# 02.net
KiCad netlist of a schematic drawn in Altium Designer
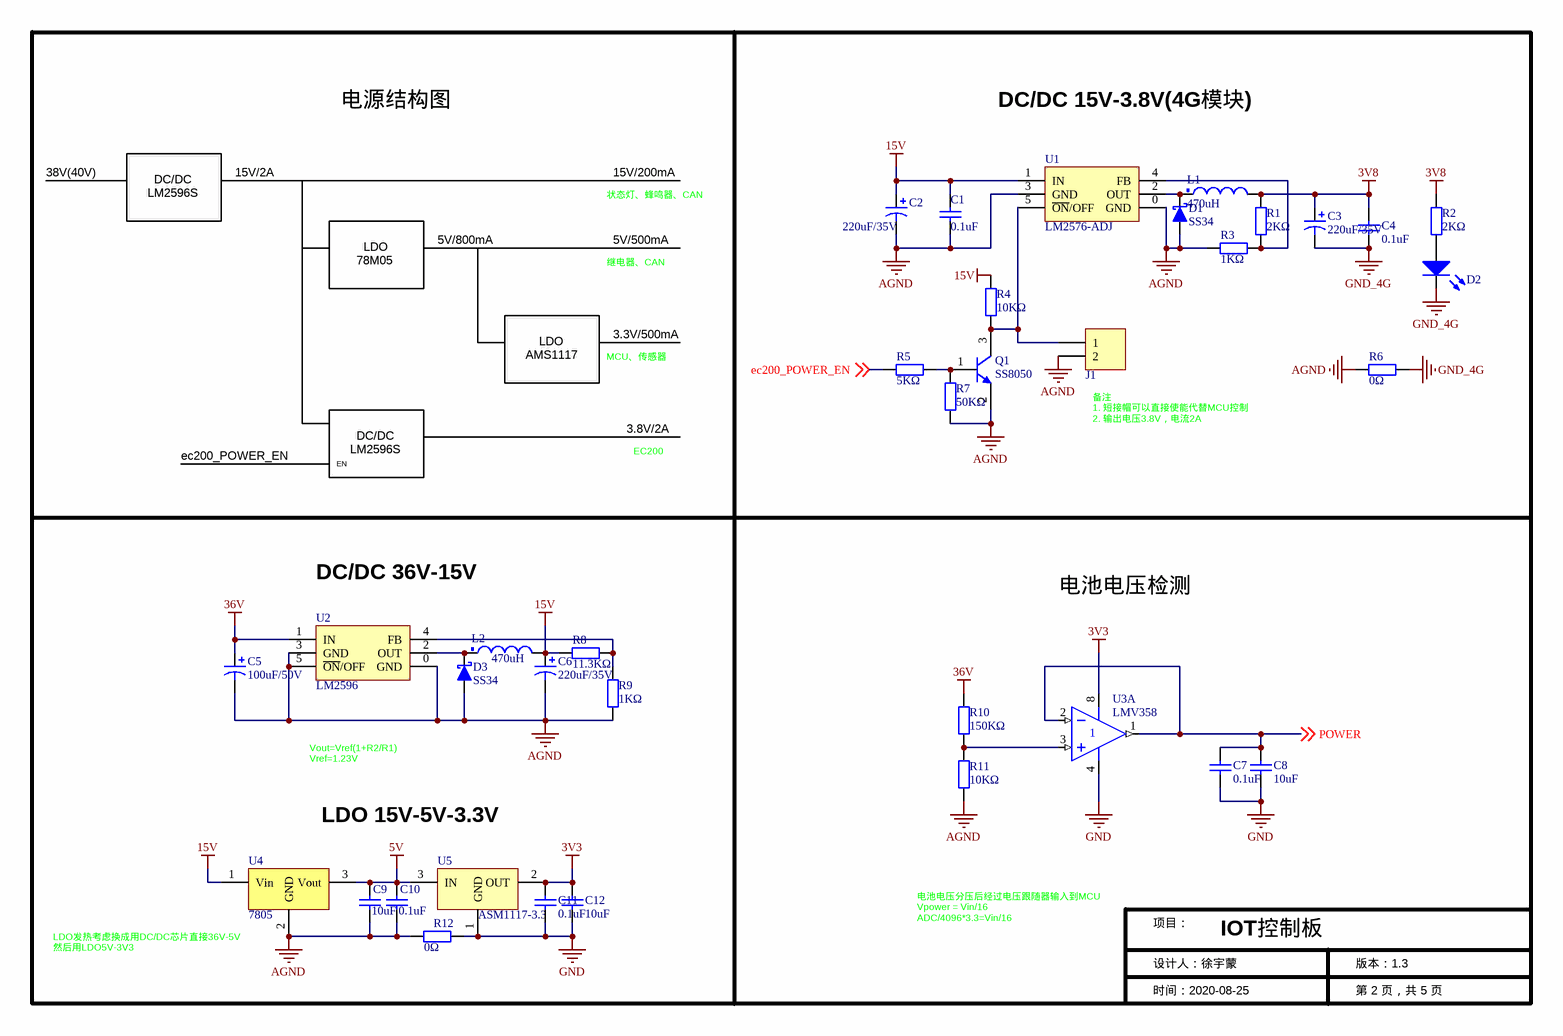
[diagram p0: 02_电源部分.SchDoc]

(export (version "E")
  (design (tool "Eeschema 10.0.6"))
  (components
    (comp (ref "C1")
      (value "0.1uF")
      (footprint "CAP-0603")
      (description "无极性电容")
      (fields (field (name "Comment") "Cap") (field (name "PUBLISHER") "Altium Limited"))
      (libsource (lib "Arrowy_Racing") (part "Cap"))
    )
    (comp (ref "C2")
      (value "220uF/35V")
      (footprint "Cap8x10.5mm")
      (description "贴片电解电容 8*10.5mm")
      (fields (field (name "Comment") "Cap Pol") (field (name "PUBLISHER") "Altium Limited"))
      (libsource (lib "元件库") (part "Cap Pol"))
    )
    (comp (ref "C3")
      (value "220uF/35V")
      (footprint "Cap8x10.5mm")
      (description "贴片电解电容 8*10.5mm")
      (fields (field (name "Comment") "Cap Pol") (field (name "PUBLISHER") "Altium Limited"))
      (libsource (lib "元件库") (part "Cap Pol"))
    )
    (comp (ref "C4")
      (value "0.1uF")
      (footprint "CAP-0603")
      (description "无极性电容")
      (fields (field (name "Comment") "Cap") (field (name "PUBLISHER") "Altium Limited"))
      (libsource (lib "Arrowy_Racing") (part "Cap"))
    )
    (comp (ref "C5")
      (value "100uF/50V")
      (footprint "Cap8x10.5mm")
      (description "贴片电解电容 8*10.5mm")
      (fields (field (name "Comment") "Cap Pol") (field (name "PUBLISHER") "Altium Limited"))
      (libsource (lib "元件库") (part "Cap Pol"))
    )
    (comp (ref "C6")
      (value "220uF/35V")
      (footprint "Cap8x10.5mm")
      (description "贴片电解电容 8*10.5mm")
      (fields (field (name "Comment") "Cap Pol") (field (name "PUBLISHER") "Altium Limited"))
      (libsource (lib "元件库") (part "Cap Pol"))
    )
    (comp (ref "C7")
      (value "0.1uF")
      (footprint "CAP-0603")
      (description "无极性电容")
      (fields (field (name "Comment") "Cap") (field (name "PUBLISHER") "Altium Limited"))
      (libsource (lib "Arrowy_Racing") (part "Cap"))
    )
    (comp (ref "C8")
      (value "10uF")
      (footprint "CAP-0603")
      (description "无极性电容")
      (fields (field (name "Comment") "Cap") (field (name "PUBLISHER") "Altium Limited"))
      (libsource (lib "Arrowy_Racing") (part "Cap"))
    )
    (comp (ref "C9")
      (value "10uF")
      (footprint "CAP-0603")
      (description "无极性电容")
      (fields (field (name "Comment") "Cap") (field (name "PUBLISHER") "Altium Limited"))
      (libsource (lib "Arrowy_Racing") (part "Cap"))
    )
    (comp (ref "C10")
      (value "0.1uF")
      (footprint "CAP-0603")
      (description "无极性电容")
      (fields (field (name "Comment") "Cap") (field (name "PUBLISHER") "Altium Limited"))
      (libsource (lib "Arrowy_Racing") (part "Cap"))
    )
    (comp (ref "C11")
      (value "0.1uF")
      (footprint "CAP-0603")
      (description "无极性电容")
      (fields (field (name "Comment") "Cap") (field (name "PUBLISHER") "Altium Limited"))
      (libsource (lib "Arrowy_Racing") (part "Cap"))
    )
    (comp (ref "C12")
      (value "10uF")
      (footprint "CAP-0603")
      (description "无极性电容")
      (fields (field (name "Comment") "Cap") (field (name "PUBLISHER") "Altium Limited"))
      (libsource (lib "Arrowy_Racing") (part "Cap"))
    )
    (comp (ref "D1")
      (value "SS34")
      (footprint "SMA(DO-214AC)")
      (description "Schottky Diode")
      (fields (field (name "PUBLISHER") "Altium Limited"))
      (libsource (lib "元件库") (part "D Schottky"))
    )
    (comp (ref "D2")
      (value "LED")
      (footprint "LED_0805")
      (description "发光二极管")
      (fields (field (name "PUBLISHER") "Altium Limited"))
      (libsource (lib "Arrowy_Racing") (part "LED"))
    )
    (comp (ref "D3")
      (value "SS34")
      (footprint "SMA(DO-214AC)")
      (description "Schottky Diode")
      (fields (field (name "PUBLISHER") "Altium Limited"))
      (libsource (lib "元件库") (part "D Schottky"))
    )
    (comp (ref "J1")
      (value "Header 2")
      (footprint "Header_2X1_2.54")
      (description "接插件")
      (fields (field (name "PUBLISHER") "Altium Limited"))
      (libsource (lib "Arrowy_Racing") (part "Header 2"))
    )
    (comp (ref "L1")
      (value "470uH")
      (footprint "CD43")
      (description "贴片功率电感")
      (fields (field (name "Comment") "Inductor") (field (name "PUBLISHER") "Altium Limited"))
      (libsource (lib "元件库") (part "Inductor"))
    )
    (comp (ref "L2")
      (value "470uH")
      (footprint "CD43")
      (description "贴片功率电感")
      (fields (field (name "Comment") "Inductor") (field (name "PUBLISHER") "Altium Limited"))
      (libsource (lib "元件库") (part "Inductor"))
    )
    (comp (ref "Q1")
      (value "SS8050")
      (footprint "SOT-23")
      (description "NPN贴片三极管")
      (fields (field (name "PUBLISHER") "Altium Limited"))
      (libsource (lib "Arrowy_Racing") (part "SS8050"))
    )
    (comp (ref "R1")
      (value "2KΩ")
      (footprint "0603")
      (description "贴片电阻")
      (fields (field (name "Comment") "Res") (field (name "PUBLISHER") "Altium Limited"))
      (libsource (lib "") (part "Res_2"))
    )
    (comp (ref "R2")
      (value "2KΩ")
      (footprint "0603")
      (description "贴片电阻")
      (fields (field (name "Comment") "Res") (field (name "PUBLISHER") "Altium Limited"))
      (libsource (lib "") (part "Res_1"))
    )
    (comp (ref "R3")
      (value "1KΩ")
      (footprint "0603")
      (description "贴片电阻")
      (fields (field (name "Comment") "Res") (field (name "PUBLISHER") "Altium Limited"))
      (libsource (lib "Arrowy_Racing") (part "Res"))
    )
    (comp (ref "R4")
      (value "10KΩ")
      (footprint "0603")
      (description "贴片电阻")
      (fields (field (name "Comment") "Res") (field (name "PUBLISHER") "Altium Limited"))
      (libsource (lib "") (part "Res_2"))
    )
    (comp (ref "R5")
      (value "5KΩ")
      (footprint "0603")
      (description "贴片电阻")
      (fields (field (name "Comment") "Res") (field (name "PUBLISHER") "Altium Limited"))
      (libsource (lib "Arrowy_Racing") (part "Res"))
    )
    (comp (ref "R6")
      (value "0Ω")
      (footprint "0805")
      (description "贴片电阻")
      (fields (field (name "Comment") "Res") (field (name "PUBLISHER") "Altium Limited"))
      (libsource (lib "Arrowy_Racing") (part "Res"))
    )
    (comp (ref "R7")
      (value "50KΩ")
      (footprint "0603")
      (description "贴片电阻")
      (fields (field (name "Comment") "Res") (field (name "PUBLISHER") "Altium Limited"))
      (libsource (lib "") (part "Res_2"))
    )
    (comp (ref "R8")
      (value "11.3KΩ")
      (footprint "0603")
      (description "贴片电阻")
      (fields (field (name "Comment") "Res") (field (name "PUBLISHER") "Altium Limited"))
      (libsource (lib "Arrowy_Racing") (part "Res"))
    )
    (comp (ref "R9")
      (value "1KΩ")
      (footprint "0603")
      (description "贴片电阻")
      (fields (field (name "Comment") "Res") (field (name "PUBLISHER") "Altium Limited"))
      (libsource (lib "") (part "Res_1"))
    )
    (comp (ref "R10")
      (value "150KΩ")
      (footprint "0603")
      (description "贴片电阻")
      (fields (field (name "Comment") "Res") (field (name "PUBLISHER") "Altium Limited"))
      (libsource (lib "") (part "Res_1"))
    )
    (comp (ref "R11")
      (value "10KΩ")
      (footprint "0603")
      (description "贴片电阻")
      (fields (field (name "Comment") "Res") (field (name "PUBLISHER") "Altium Limited"))
      (libsource (lib "") (part "Res_1"))
    )
    (comp (ref "R12")
      (value "0Ω")
      (footprint "0805")
      (description "贴片电阻")
      (fields (field (name "Comment") "Res") (field (name "PUBLISHER") "Altium Limited"))
      (libsource (lib "Arrowy_Racing") (part "Res"))
    )
    (comp (ref "U1")
      (value "LM2576-ADJ")
      (footprint "TO-263-5 无背面散热")
      (libsource (lib "Arrowy_Racing") (part "LM2576"))
    )
    (comp (ref "U2")
      (value "LM2596")
      (footprint "TO-263-5 无背面散热")
      (description "DC/DC")
      (libsource (lib "Arrowy_Racing") (part "LM2596"))
    )
    (comp (ref "U3")
      (value "LMV358")
      (footprint "OPA2350")
      (fields (field (name "PUBLISHER") "Altium Limited"))
      (libsource (lib "元件库") (part "LMV358"))
    )
    (comp (ref "U4")
      (value "7805")
      (footprint "TO-252")
      (description "三端稳压器7805")
      (libsource (lib "Arrowy_Racing") (part "7805"))
    )
    (comp (ref "U5")
      (value "ASM1117-3.3")
      (footprint "SOT-223")
      (description "3.3V稳压芯片")
      (libsource (lib "Arrowy_Racing") (part "ASM1117"))
    )
  )
  (nets
    (net (code "1") (name "3V3") (class "Default")
      (node (ref "C11") (pin "2") (pinfunction "2_2") (pintype "passive"))
      (node (ref "C12") (pin "2") (pinfunction "2_2") (pintype "passive"))
      (node (ref "U3") (pin "8") (pinfunction "V+_8") (pintype "power_in"))
      (node (ref "U5") (pin "2") (pinfunction "OUT_2") (pintype "passive"))
    )
    (net (code "2") (name "3V8") (class "Default")
      (node (ref "C3") (pin "1") (pinfunction "1_1") (pintype "passive"))
      (node (ref "C4") (pin "2") (pinfunction "2_2") (pintype "passive"))
      (node (ref "L1") (pin "2") (pinfunction "2_2") (pintype "passive"))
      (node (ref "R1") (pin "1") (pinfunction "1_1") (pintype "passive"))
      (node (ref "R2") (pin "2") (pinfunction "2_2") (pintype "passive"))
    )
    (net (code "3") (name "5V") (class "Default")
      (node (ref "C10") (pin "2") (pinfunction "2_2") (pintype "passive"))
      (node (ref "C9") (pin "2") (pinfunction "2_2") (pintype "passive"))
      (node (ref "U4") (pin "3") (pinfunction "Vout_3") (pintype "passive"))
      (node (ref "U5") (pin "3") (pinfunction "IN_3") (pintype "passive"))
    )
    (net (code "4") (name "15V") (class "Default")
      (node (ref "C1") (pin "2") (pinfunction "2_2") (pintype "passive"))
      (node (ref "C2") (pin "1") (pinfunction "1_1") (pintype "passive"))
      (node (ref "C6") (pin "1") (pinfunction "1_1") (pintype "passive"))
      (node (ref "L2") (pin "2") (pinfunction "2_2") (pintype "passive"))
      (node (ref "R4") (pin "1") (pinfunction "1_1") (pintype "passive"))
      (node (ref "R8") (pin "1") (pinfunction "1_1") (pintype "passive"))
      (node (ref "U1") (pin "1") (pinfunction "IN_1") (pintype "passive"))
      (node (ref "U4") (pin "1") (pinfunction "Vin_1") (pintype "passive"))
    )
    (net (code "5") (name "36V") (class "Default")
      (node (ref "C5") (pin "1") (pinfunction "1_1") (pintype "passive"))
      (node (ref "R10") (pin "2") (pinfunction "2_2") (pintype "passive"))
      (node (ref "U2") (pin "1") (pinfunction "IN_1") (pintype "passive"))
    )
    (net (code "6") (name "AGND") (class "Default")
      (node (ref "C1") (pin "1") (pinfunction "1_1") (pintype "passive"))
      (node (ref "C10") (pin "1") (pinfunction "1_1") (pintype "passive"))
      (node (ref "C2") (pin "2") (pinfunction "2_2") (pintype "passive"))
      (node (ref "C5") (pin "2") (pinfunction "2_2") (pintype "passive"))
      (node (ref "C6") (pin "2") (pinfunction "2_2") (pintype "passive"))
      (node (ref "C9") (pin "1") (pinfunction "1_1") (pintype "passive"))
      (node (ref "D1") (pin "1") (pinfunction "A_1") (pintype "passive"))
      (node (ref "D3") (pin "1") (pinfunction "A_1") (pintype "passive"))
      (node (ref "J1") (pin "2") (pinfunction "2_2") (pintype "passive"))
      (node (ref "Q1") (pin "2") (pinfunction "E_2") (pintype "passive"))
      (node (ref "R11") (pin "1") (pinfunction "1_1") (pintype "passive"))
      (node (ref "R12") (pin "1") (pinfunction "1_1") (pintype "passive"))
      (node (ref "R3") (pin "1") (pinfunction "1_1") (pintype "passive"))
      (node (ref "R6") (pin "1") (pinfunction "1_1") (pintype "passive"))
      (node (ref "R7") (pin "2") (pinfunction "2_2") (pintype "passive"))
      (node (ref "R9") (pin "1") (pinfunction "1_1") (pintype "passive"))
      (node (ref "U1") (pin "0") (pinfunction "GND_0") (pintype "passive"))
      (node (ref "U1") (pin "3") (pinfunction "GND_3") (pintype "passive"))
      (node (ref "U2") (pin "0") (pinfunction "GND_0") (pintype "passive"))
      (node (ref "U2") (pin "3") (pinfunction "GND_3") (pintype "passive"))
      (node (ref "U2") (pin "5") (pinfunction "~{ON}/OFF_5") (pintype "passive"))
      (node (ref "U4") (pin "2") (pinfunction "GND_2") (pintype "passive"))
    )
    (net (code "7") (name "GND") (class "Default")
      (node (ref "C11") (pin "1") (pinfunction "1_1") (pintype "passive"))
      (node (ref "C12") (pin "1") (pinfunction "1_1") (pintype "passive"))
      (node (ref "C7") (pin "1") (pinfunction "1_1") (pintype "passive"))
      (node (ref "C8") (pin "1") (pinfunction "1_1") (pintype "passive"))
      (node (ref "R12") (pin "2") (pinfunction "2_2") (pintype "passive"))
      (node (ref "U3") (pin "4") (pinfunction "V-_4") (pintype "power_in"))
      (node (ref "U5") (pin "1") (pinfunction "GND_1") (pintype "passive"))
    )
    (net (code "8") (name "GND_4G") (class "Default")
      (node (ref "C3") (pin "2") (pinfunction "2_2") (pintype "passive"))
      (node (ref "C4") (pin "1") (pinfunction "1_1") (pintype "passive"))
      (node (ref "D2") (pin "2") (pinfunction "K_2") (pintype "passive"))
      (node (ref "R6") (pin "2") (pinfunction "2_2") (pintype "passive"))
    )
    (net (code "9") (name "Net-(D1-K)") (class "Default")
      (node (ref "D1") (pin "2") (pinfunction "K_2") (pintype "passive"))
      (node (ref "L1") (pin "1") (pinfunction "1_1") (pintype "passive"))
      (node (ref "U1") (pin "2") (pinfunction "OUT_2") (pintype "passive"))
    )
    (net (code "10") (name "Net-(D2-A)") (class "Default")
      (node (ref "D2") (pin "1") (pinfunction "A_1") (pintype "passive"))
      (node (ref "R2") (pin "1") (pinfunction "1_1") (pintype "passive"))
    )
    (net (code "11") (name "Net-(D3-K)") (class "Default")
      (node (ref "D3") (pin "2") (pinfunction "K_2") (pintype "passive"))
      (node (ref "L2") (pin "1") (pinfunction "1_1") (pintype "passive"))
      (node (ref "U2") (pin "2") (pinfunction "OUT_2") (pintype "passive"))
    )
    (net (code "12") (name "Net-(Q1-B)") (class "Default")
      (node (ref "Q1") (pin "1") (pinfunction "B_1") (pintype "passive"))
      (node (ref "R5") (pin "2") (pinfunction "2_2") (pintype "passive"))
      (node (ref "R7") (pin "1") (pinfunction "1_1") (pintype "passive"))
    )
    (net (code "13") (name "Net-(Q1-C)") (class "Default")
      (node (ref "J1") (pin "1") (pinfunction "1_1") (pintype "passive"))
      (node (ref "Q1") (pin "3") (pinfunction "C_3") (pintype "passive"))
      (node (ref "R4") (pin "2") (pinfunction "2_2") (pintype "passive"))
      (node (ref "U1") (pin "5") (pinfunction "~{ON}/OFF_5") (pintype "passive"))
    )
    (net (code "14") (name "Net-(U1-FB)") (class "Default")
      (node (ref "R1") (pin "2") (pinfunction "2_2") (pintype "passive"))
      (node (ref "R3") (pin "2") (pinfunction "2_2") (pintype "passive"))
      (node (ref "U1") (pin "4") (pinfunction "FB_4") (pintype "passive"))
    )
    (net (code "15") (name "Net-(U2-FB)") (class "Default")
      (node (ref "R8") (pin "2") (pinfunction "2_2") (pintype "passive"))
      (node (ref "R9") (pin "2") (pinfunction "2_2") (pintype "passive"))
      (node (ref "U2") (pin "4") (pinfunction "FB_4") (pintype "passive"))
    )
    (net (code "16") (name "Net-(U3A-IN+)") (class "Default")
      (node (ref "R10") (pin "1") (pinfunction "1_1") (pintype "passive"))
      (node (ref "R11") (pin "2") (pinfunction "2_2") (pintype "passive"))
      (node (ref "U3") (pin "3") (pinfunction "IN+_3") (pintype "input"))
    )
    (net (code "17") (name "POWER") (class "Default")
      (node (ref "C7") (pin "2") (pinfunction "2_2") (pintype "passive"))
      (node (ref "C8") (pin "2") (pinfunction "2_2") (pintype "passive"))
      (node (ref "U3") (pin "1") (pinfunction "OUT_1") (pintype "output"))
      (node (ref "U3") (pin "2") (pinfunction "IN-_2") (pintype "input"))
    )
    (net (code "18") (name "ec200_POWER_EN") (class "Default")
      (node (ref "R5") (pin "1") (pinfunction "1_1") (pintype "passive"))
    )
  )
)
